# RP2040.net
KiCad netlist of a schematic drawn in Altium Designer
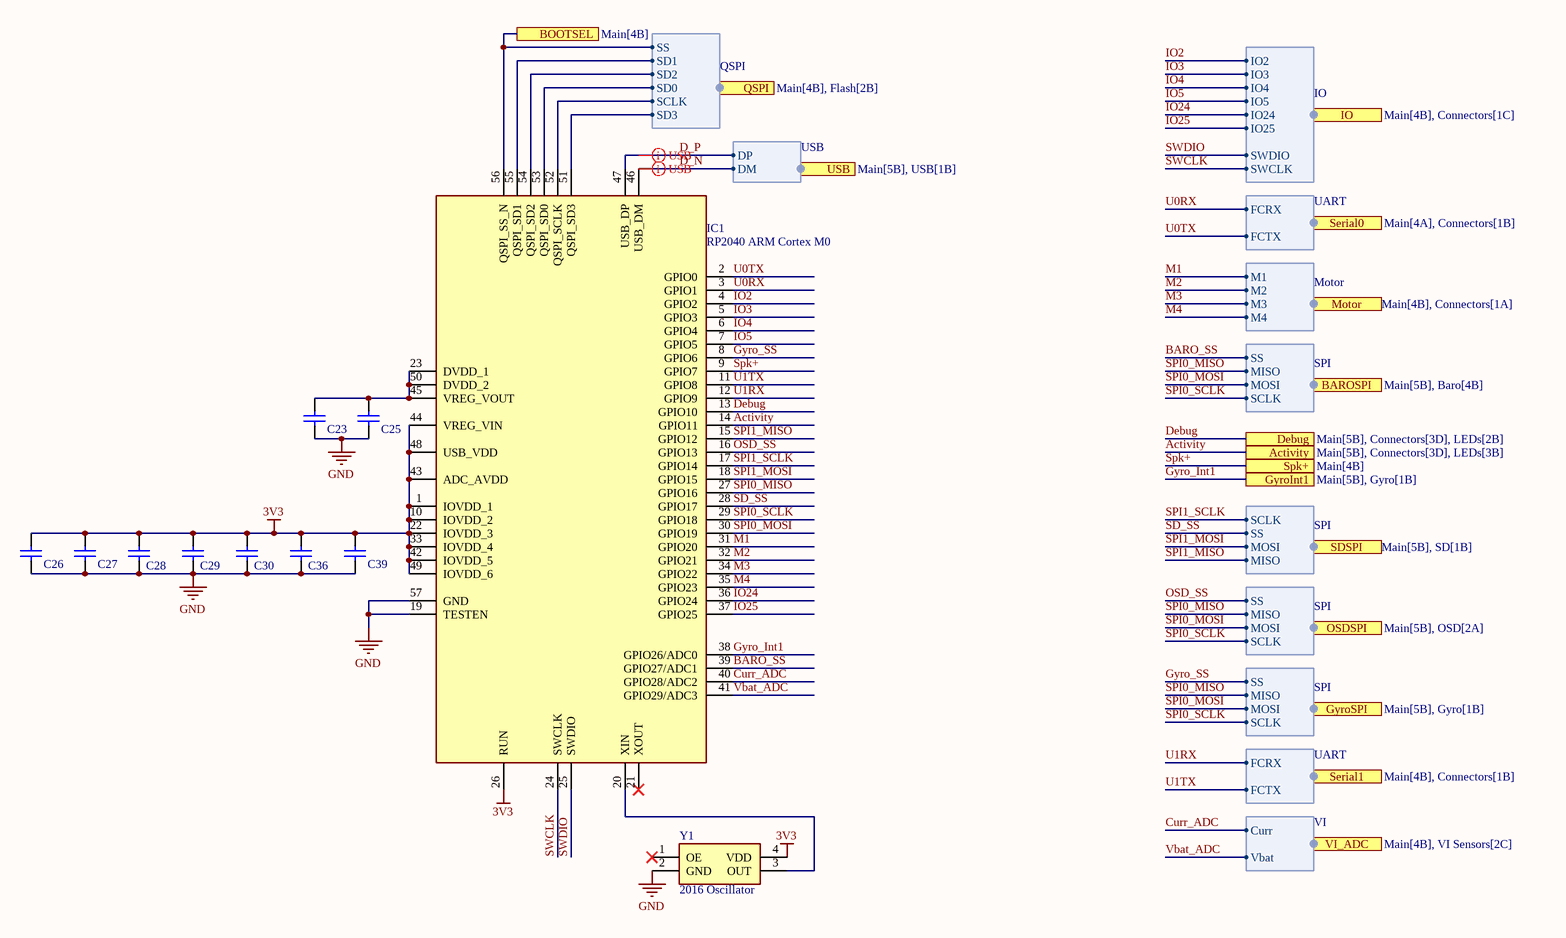
[diagram p0: RP2040.SchDoc]

(export (version "E")
  (design (tool "Eeschema 10.0.6"))
  (components
    (comp (ref "C23")
      (value "100nF")
      (footprint "WCAP-CSGP_0402_L1W0.5H0.5")
      (description "WCAP-CSGP Multilayer Ceramic Chip Capacitor, General Purpose, size 0402, X7R, 100nF, 50VDC")
      (fields
        (field (name "MANUFACTURER PART NUMBER") "885012205086")
        (field (name "MANUFACTURER") "Wurth Elektronik")
      )
      (libsource (lib "Altium_WCAP-CSGP (rev22f)") (part "885012205086"))
    )
    (comp (ref "C25")
      (value "100nF")
      (footprint "WCAP-CSGP_0402_L1W0.5H0.5")
      (description "WCAP-CSGP Multilayer Ceramic Chip Capacitor, General Purpose, size 0402, X7R, 100nF, 50VDC")
      (fields
        (field (name "MANUFACTURER PART NUMBER") "885012205086")
        (field (name "MANUFACTURER") "Wurth Elektronik")
      )
      (libsource (lib "Altium_WCAP-CSGP (rev22f)") (part "885012205086"))
    )
    (comp (ref "C26")
      (value "100nF")
      (footprint "WCAP-CSGP_0402_L1W0.5H0.5")
      (description "WCAP-CSGP Multilayer Ceramic Chip Capacitor, General Purpose, size 0402, X7R, 100nF, 50VDC")
      (fields
        (field (name "MANUFACTURER PART NUMBER") "885012205086")
        (field (name "MANUFACTURER") "Wurth Elektronik")
      )
      (libsource (lib "Altium_WCAP-CSGP (rev22f)") (part "885012205086"))
    )
    (comp (ref "C27")
      (value "100nF")
      (footprint "WCAP-CSGP_0402_L1W0.5H0.5")
      (description "WCAP-CSGP Multilayer Ceramic Chip Capacitor, General Purpose, size 0402, X7R, 100nF, 50VDC")
      (fields
        (field (name "MANUFACTURER PART NUMBER") "885012205086")
        (field (name "MANUFACTURER") "Wurth Elektronik")
      )
      (libsource (lib "Altium_WCAP-CSGP (rev22f)") (part "885012205086"))
    )
    (comp (ref "C28")
      (value "100nF")
      (footprint "WCAP-CSGP_0603_L1.6W0.8H0.8_Reflow")
      (description "WCAP-CSGP Multilayer Ceramic Chip Capacitor, General Purpose, size 0603, X7R, 100nF, 50VDC")
      (fields
        (field (name "MANUFACTURER PART NUMBER") "885012206095")
        (field (name "MANUFACTURER") "Wurth Elektronik")
      )
      (libsource (lib "Altium_WCAP-CSGP (rev22f)") (part "885012206095"))
    )
    (comp (ref "C29")
      (value "100nF")
      (footprint "WCAP-CSGP_0603_L1.6W0.8H0.8_Reflow")
      (description "WCAP-CSGP Multilayer Ceramic Chip Capacitor, General Purpose, size 0603, X7R, 100nF, 50VDC")
      (fields
        (field (name "MANUFACTURER PART NUMBER") "885012206095")
        (field (name "MANUFACTURER") "Wurth Elektronik")
      )
      (libsource (lib "Altium_WCAP-CSGP (rev22f)") (part "885012206095"))
    )
    (comp (ref "C30")
      (value "100nF")
      (footprint "WCAP-CSGP_0603_L1.6W0.8H0.8_Reflow")
      (description "WCAP-CSGP Multilayer Ceramic Chip Capacitor, General Purpose, size 0603, X7R, 100nF, 50VDC")
      (fields
        (field (name "MANUFACTURER PART NUMBER") "885012206095")
        (field (name "MANUFACTURER") "Wurth Elektronik")
      )
      (libsource (lib "Altium_WCAP-CSGP (rev22f)") (part "885012206095"))
    )
    (comp (ref "C36")
      (value "100nF")
      (footprint "WCAP-CSGP_0603_L1.6W0.8H0.8_Reflow")
      (description "WCAP-CSGP Multilayer Ceramic Chip Capacitor, General Purpose, size 0603, X7R, 100nF, 50VDC")
      (fields
        (field (name "MANUFACTURER PART NUMBER") "885012206095")
        (field (name "MANUFACTURER") "Wurth Elektronik")
      )
      (libsource (lib "Altium_WCAP-CSGP (rev22f)") (part "885012206095"))
    )
    (comp (ref "C39")
      (value "100nF")
      (footprint "WCAP-CSGP_0402_L1W0.5H0.5")
      (description "WCAP-CSGP Multilayer Ceramic Chip Capacitor, General Purpose, size 0402, X7R, 100nF, 50VDC")
      (fields
        (field (name "MANUFACTURER PART NUMBER") "885012205086")
        (field (name "MANUFACTURER") "Wurth Elektronik")
      )
      (libsource (lib "Altium_WCAP-CSGP (rev22f)") (part "885012205086"))
    )
    (comp (ref "IC1")
      (value "RP2040 ARM Cortex M0")
      (footprint "Custom Components:SC091413")
      (description "Microcontroller")
      (fields
        (field (name "MANUFACTURER_PART_NUMBER") "SC0914(13)")
        (field (name "MOUSER PART NUMBER") "358-SC091413")
      )
      (libsource (lib "Custom Components") (part "RP2040"))
    )
    (comp (ref "Y1")
      (value "2016 Oscillator")
      (footprint "Custom Components:2016 Oscillator")
      (description "YXC OT201612MJBA4SL")
      (fields
        (field (name "MANUFACTURER_PART_NUMBER") "DSC6003MA3B-032K768")
        (field (name "MOUSER PART NUMBER") "579-6003MA3B032K768")
      )
      (libsource (lib "Custom Components") (part "2016 Oscillator"))
    )
  )
  (nets
    (net (code "8") (name "/Activity") (class "Default")
      (node (ref "IC1") (pin "14") (pinfunction "GPIO11_14") (pintype "passive"))
    )
    (net (code "9") (name "/BARO_SS") (class "Default")
      (node (ref "IC1") (pin "39") (pinfunction "GPIO27/ADC1_39") (pintype "passive"))
    )
    (net (code "10") (name "/BOOTSEL") (class "Default")
      (node (ref "IC1") (pin "56") (pinfunction "QSPI_SS_N_56") (pintype "passive"))
    )
    (net (code "11") (name "/Curr_ADC") (class "Default")
      (node (ref "IC1") (pin "40") (pinfunction "GPIO28/ADC2_40") (pintype "passive"))
    )
    (net (code "12") (name "/D_N") (class "Default")
      (node (ref "IC1") (pin "46") (pinfunction "USB_DM_46") (pintype "passive"))
    )
    (net (code "13") (name "/D_P") (class "Default")
      (node (ref "IC1") (pin "47") (pinfunction "USB_DP_47") (pintype "passive"))
    )
    (net (code "14") (name "/Debug") (class "Default")
      (node (ref "IC1") (pin "13") (pinfunction "GPIO10_13") (pintype "passive"))
    )
    (net (code "15") (name "/Gyro_Int1") (class "Default")
      (node (ref "IC1") (pin "38") (pinfunction "GPIO26/ADC0_38") (pintype "passive"))
    )
    (net (code "16") (name "/Gyro_SS") (class "Default")
      (node (ref "IC1") (pin "8") (pinfunction "GPIO6_8") (pintype "passive"))
    )
    (net (code "17") (name "/IO2") (class "Default")
      (node (ref "IC1") (pin "4") (pinfunction "GPIO2_4") (pintype "passive"))
    )
    (net (code "18") (name "/IO3") (class "Default")
      (node (ref "IC1") (pin "5") (pinfunction "GPIO3_5") (pintype "passive"))
    )
    (net (code "19") (name "/IO4") (class "Default")
      (node (ref "IC1") (pin "6") (pinfunction "GPIO4_6") (pintype "passive"))
    )
    (net (code "20") (name "/IO5") (class "Default")
      (node (ref "IC1") (pin "7") (pinfunction "GPIO5_7") (pintype "passive"))
    )
    (net (code "21") (name "/IO24") (class "Default")
      (node (ref "IC1") (pin "36") (pinfunction "GPIO24_36") (pintype "passive"))
    )
    (net (code "22") (name "/IO25") (class "Default")
      (node (ref "IC1") (pin "37") (pinfunction "GPIO25_37") (pintype "passive"))
    )
    (net (code "23") (name "/M1") (class "Default")
      (node (ref "IC1") (pin "31") (pinfunction "GPIO20_31") (pintype "passive"))
    )
    (net (code "24") (name "/M2") (class "Default")
      (node (ref "IC1") (pin "32") (pinfunction "GPIO21_32") (pintype "passive"))
    )
    (net (code "25") (name "/M3") (class "Default")
      (node (ref "IC1") (pin "34") (pinfunction "GPIO22_34") (pintype "passive"))
    )
    (net (code "26") (name "/M4") (class "Default")
      (node (ref "IC1") (pin "35") (pinfunction "GPIO23_35") (pintype "passive"))
    )
    (net (code "27") (name "/OSD_SS") (class "Default")
      (node (ref "IC1") (pin "16") (pinfunction "GPIO13_16") (pintype "passive"))
    )
    (net (code "28") (name "/SD0") (class "Default")
      (node (ref "IC1") (pin "53") (pinfunction "QSPI_SD0_53") (pintype "passive"))
    )
    (net (code "29") (name "/SD1") (class "Default")
      (node (ref "IC1") (pin "55") (pinfunction "QSPI_SD1_55") (pintype "passive"))
    )
    (net (code "30") (name "/SD2") (class "Default")
      (node (ref "IC1") (pin "54") (pinfunction "QSPI_SD2_54") (pintype "passive"))
    )
    (net (code "31") (name "/SD3") (class "Default")
      (node (ref "IC1") (pin "51") (pinfunction "QSPI_SD3_51") (pintype "passive"))
    )
    (net (code "32") (name "/SD_SS") (class "Default")
      (node (ref "IC1") (pin "28") (pinfunction "GPIO17_28") (pintype "passive"))
    )
    (net (code "33") (name "/SPI0_MISO") (class "Default")
      (node (ref "IC1") (pin "27") (pinfunction "GPIO16_27") (pintype "passive"))
    )
    (net (code "34") (name "/SPI0_MOSI") (class "Default")
      (node (ref "IC1") (pin "30") (pinfunction "GPIO19_30") (pintype "passive"))
    )
    (net (code "35") (name "/SPI0_SCLK") (class "Default")
      (node (ref "IC1") (pin "29") (pinfunction "GPIO18_29") (pintype "passive"))
    )
    (net (code "36") (name "/SPI1_MISO") (class "Default")
      (node (ref "IC1") (pin "15") (pinfunction "GPIO12_15") (pintype "passive"))
    )
    (net (code "37") (name "/SPI1_MOSI") (class "Default")
      (node (ref "IC1") (pin "18") (pinfunction "GPIO15_18") (pintype "passive"))
    )
    (net (code "38") (name "/SPI1_SCLK") (class "Default")
      (node (ref "IC1") (pin "17") (pinfunction "GPIO14_17") (pintype "passive"))
    )
    (net (code "39") (name "/SWCLK") (class "Default")
      (node (ref "IC1") (pin "24") (pinfunction "SWCLK_24") (pintype "passive"))
    )
    (net (code "40") (name "/SWDIO") (class "Default")
      (node (ref "IC1") (pin "25") (pinfunction "SWDIO_25") (pintype "passive"))
    )
    (net (code "41") (name "/Spk+") (class "Default")
      (node (ref "IC1") (pin "9") (pinfunction "GPIO7_9") (pintype "passive"))
    )
    (net (code "42") (name "/U0RX") (class "Default")
      (node (ref "IC1") (pin "3") (pinfunction "GPIO1_3") (pintype "passive"))
    )
    (net (code "43") (name "/U0TX") (class "Default")
      (node (ref "IC1") (pin "2") (pinfunction "GPIO0_2") (pintype "passive"))
    )
    (net (code "44") (name "/U1RX") (class "Default")
      (node (ref "IC1") (pin "12") (pinfunction "GPIO9_12") (pintype "passive"))
    )
    (net (code "45") (name "/U1TX") (class "Default")
      (node (ref "IC1") (pin "11") (pinfunction "GPIO8_11") (pintype "passive"))
    )
    (net (code "46") (name "/Vbat_ADC") (class "Default")
      (node (ref "IC1") (pin "41") (pinfunction "GPIO29/ADC3_41") (pintype "passive"))
    )
    (net (code "54") (name "3V3") (class "Default")
      (node (ref "C26") (pin "2") (pinfunction "2_2") (pintype "passive"))
      (node (ref "C27") (pin "2") (pinfunction "2_2") (pintype "passive"))
      (node (ref "C28") (pin "2") (pinfunction "2_2") (pintype "passive"))
      (node (ref "C29") (pin "2") (pinfunction "2_2") (pintype "passive"))
      (node (ref "C30") (pin "2") (pinfunction "2_2") (pintype "passive"))
      (node (ref "C36") (pin "2") (pinfunction "2_2") (pintype "passive"))
      (node (ref "C39") (pin "2") (pinfunction "2_2") (pintype "passive"))
      (node (ref "IC1") (pin "1") (pinfunction "IOVDD_1_1") (pintype "passive"))
      (node (ref "IC1") (pin "10") (pinfunction "IOVDD_2_10") (pintype "passive"))
      (node (ref "IC1") (pin "22") (pinfunction "IOVDD_3_22") (pintype "passive"))
      (node (ref "IC1") (pin "26") (pinfunction "RUN_26") (pintype "passive"))
      (node (ref "IC1") (pin "33") (pinfunction "IOVDD_4_33") (pintype "passive"))
      (node (ref "IC1") (pin "42") (pinfunction "IOVDD_5_42") (pintype "passive"))
      (node (ref "IC1") (pin "43") (pinfunction "ADC_AVDD_43") (pintype "passive"))
      (node (ref "IC1") (pin "44") (pinfunction "VREG_VIN_44") (pintype "passive"))
      (node (ref "IC1") (pin "48") (pinfunction "USB_VDD_48") (pintype "passive"))
      (node (ref "IC1") (pin "49") (pinfunction "IOVDD_6_49") (pintype "passive"))
      (node (ref "Y1") (pin "4") (pinfunction "VDD_4") (pintype "passive"))
    )
    (net (code "55") (name "GND") (class "Default")
      (node (ref "C23") (pin "1") (pinfunction "1_1") (pintype "passive"))
      (node (ref "C25") (pin "1") (pinfunction "1_1") (pintype "passive"))
      (node (ref "C26") (pin "1") (pinfunction "1_1") (pintype "passive"))
      (node (ref "C27") (pin "1") (pinfunction "1_1") (pintype "passive"))
      (node (ref "C28") (pin "1") (pinfunction "1_1") (pintype "passive"))
      (node (ref "C29") (pin "1") (pinfunction "1_1") (pintype "passive"))
      (node (ref "C30") (pin "1") (pinfunction "1_1") (pintype "passive"))
      (node (ref "C36") (pin "1") (pinfunction "1_1") (pintype "passive"))
      (node (ref "C39") (pin "1") (pinfunction "1_1") (pintype "passive"))
      (node (ref "IC1") (pin "19") (pinfunction "TESTEN_19") (pintype "passive"))
      (node (ref "IC1") (pin "57") (pinfunction "GND_57") (pintype "passive"))
      (node (ref "Y1") (pin "2") (pinfunction "GND_2") (pintype "passive"))
    )
    (net (code "56") (name "Net-(IC1-DVDD_1)") (class "Default")
      (node (ref "C23") (pin "2") (pinfunction "2_2") (pintype "passive"))
      (node (ref "C25") (pin "2") (pinfunction "2_2") (pintype "passive"))
      (node (ref "IC1") (pin "23") (pinfunction "DVDD_1_23") (pintype "passive"))
      (node (ref "IC1") (pin "45") (pinfunction "VREG_VOUT_45") (pintype "passive"))
      (node (ref "IC1") (pin "50") (pinfunction "DVDD_2_50") (pintype "passive"))
    )
    (net (code "57") (name "Net-(IC1-XIN)") (class "Default")
      (node (ref "IC1") (pin "20") (pinfunction "XIN_20") (pintype "passive"))
      (node (ref "Y1") (pin "3") (pinfunction "OUT_3") (pintype "passive"))
    )
    (net (code "58") (name "unconnected-(IC1-QSPI_SCLK-Pad52)") (class "Default")
      (node (ref "IC1") (pin "52") (pinfunction "QSPI_SCLK_52") (pintype "passive"))
    )
    (net (code "59") (name "unconnected-(IC1-XOUT-Pad21)") (class "Default")
      (node (ref "IC1") (pin "21") (pinfunction "XOUT_21") (pintype "passive+no_connect"))
    )
    (net (code "60") (name "unconnected-(Y1-OE-Pad1)") (class "Default")
      (node (ref "Y1") (pin "1") (pinfunction "OE_1") (pintype "passive+no_connect"))
    )
  )
)
